# STM32.net
KiCad netlist of a schematic drawn in Altium Designer
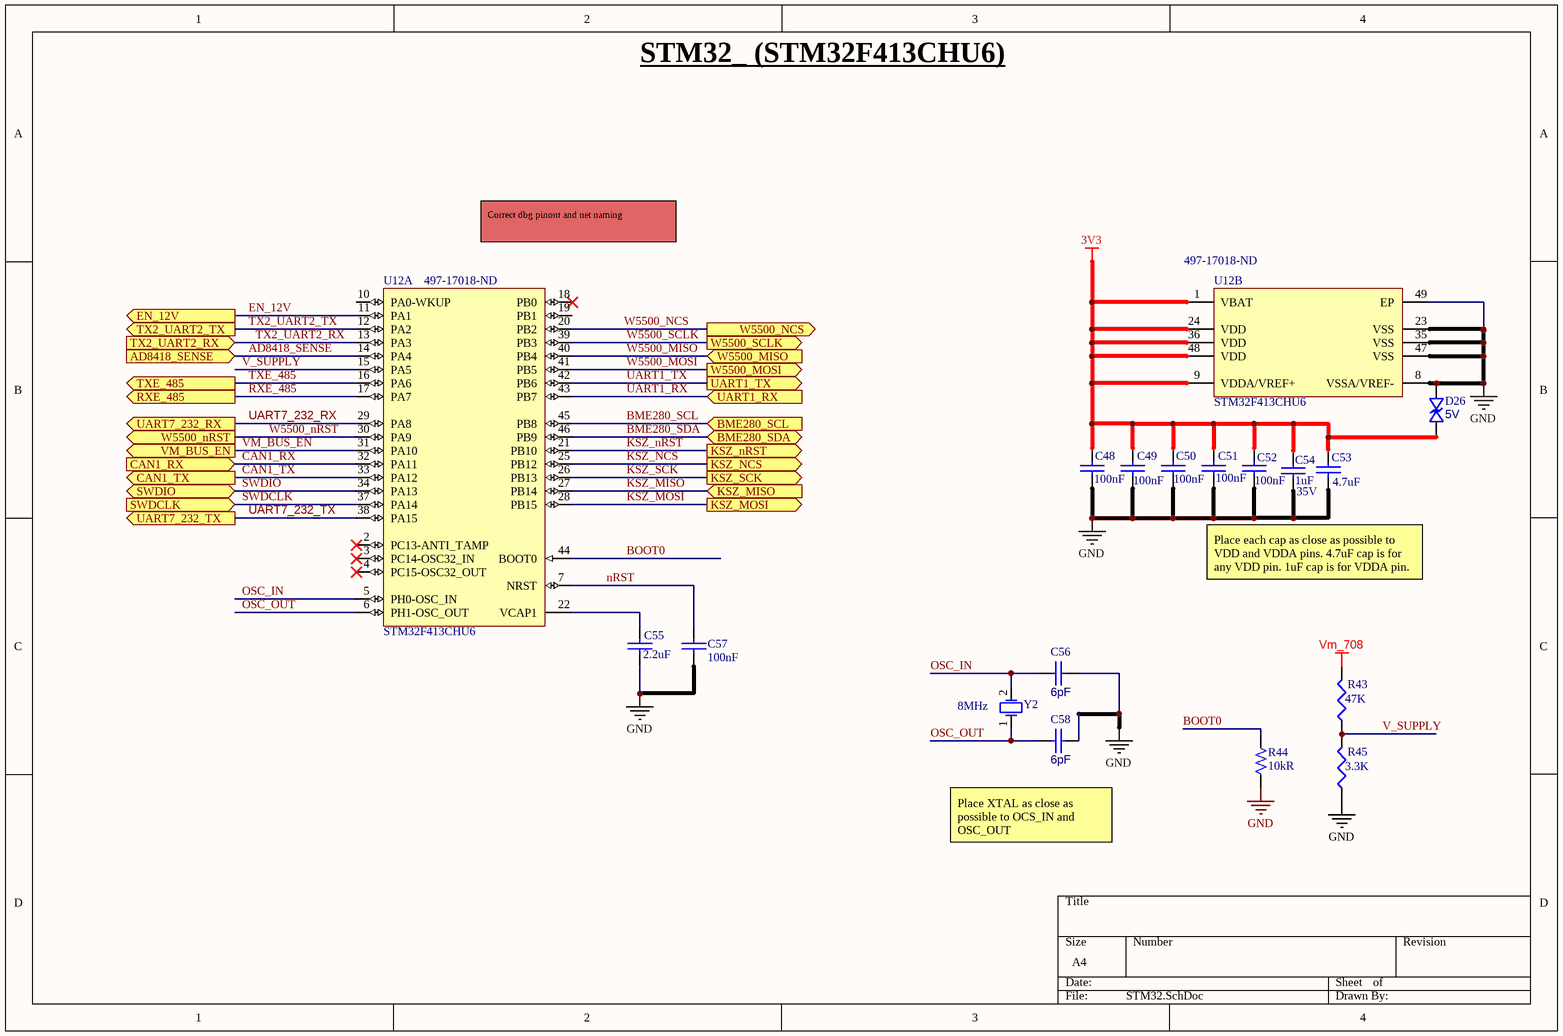
[diagram p0: STM32.SchDoc]

(export (version "E")
  (design (tool "Eeschema 10.0.6"))
  (components
    (comp (ref "C48")
      (value "Capacitor")
      (footprint "CAP0402")
      (fields
        (field (name "MANUFACTURER") "TDK")
        (field (name "MANUFACTURER PART NUMBER") "CGA2B3X7R1H104K050BB")
        (field (name "CAPACITANCE") "100nF")
        (field (name "TOLERANCE") "10%")
      )
      (libsource (lib "") (part "Capacitor_1"))
    )
    (comp (ref "C49")
      (value "Capacitor")
      (footprint "CAP0402")
      (fields
        (field (name "MANUFACTURER") "TDK")
        (field (name "MANUFACTURER PART NUMBER") "CGA2B3X7R1H104K050BB")
        (field (name "CAPACITANCE") "100nF")
        (field (name "TOLERANCE") "10%")
      )
      (libsource (lib "") (part "Capacitor_1"))
    )
    (comp (ref "C50")
      (value "Capacitor")
      (footprint "CAP0402")
      (fields
        (field (name "MANUFACTURER") "TDK")
        (field (name "MANUFACTURER PART NUMBER") "CGA2B3X7R1H104K050BB")
        (field (name "CAPACITANCE") "100nF")
        (field (name "TOLERANCE") "10%")
      )
      (libsource (lib "") (part "Capacitor_1"))
    )
    (comp (ref "C51")
      (value "Capacitor")
      (footprint "CAP0402")
      (fields
        (field (name "MANUFACTURER") "TDK")
        (field (name "MANUFACTURER PART NUMBER") "CGA2B3X7R1H104K050BB")
        (field (name "CAPACITANCE") "100nF")
        (field (name "TOLERANCE") "10%")
      )
      (libsource (lib "") (part "Capacitor_1"))
    )
    (comp (ref "C52")
      (value "Capacitor")
      (footprint "CAP0402")
      (fields
        (field (name "MANUFACTURER") "TDK")
        (field (name "MANUFACTURER PART NUMBER") "CGA2B3X7R1H104K050BB")
        (field (name "CAPACITANCE") "100nF")
        (field (name "TOLERANCE") "10%")
      )
      (libsource (lib "") (part "Capacitor_1"))
    )
    (comp (ref "C53")
      (value "Capacitor")
      (footprint "CAP0402")
      (fields (field (name "CAPACITANCE") "4.7uF"))
      (libsource (lib "") (part "Capacitor_1"))
    )
    (comp (ref "C54")
      (value "Capacitor")
      (footprint "CAP0402")
      (fields (field (name "VOLTAGE RATING") "35V") (field (name "CAPACITANCE") "1uF"))
      (libsource (lib "") (part "Capacitor_1"))
    )
    (comp (ref "C55")
      (value "Capacitor")
      (footprint "CAP0402")
      (fields (field (name "CAPACITANCE") "2.2uF"))
      (libsource (lib "BPL-ShematicLibrary") (part "Capacitor"))
    )
    (comp (ref "C56")
      (value "Capacitor")
      (footprint "CAP0402")
      (description "CAP CER 6PF 100V C0G/NP0 0402")
      (fields (field (name "CAPACITANCE") "6pF"))
      (libsource (lib "BPL-ShematicLibrary") (part "Capacitor"))
    )
    (comp (ref "C57")
      (value "Capacitor")
      (footprint "CAP0402")
      (fields
        (field (name "MANUFACTURER") "TDK")
        (field (name "MANUFACTURER PART NUMBER") "CGA2B3X7R1H104K050BB")
        (field (name "CAPACITANCE") "100nF")
        (field (name "TOLERANCE") "10%")
      )
      (libsource (lib "") (part "Capacitor_1"))
    )
    (comp (ref "C58")
      (value "Capacitor")
      (footprint "CAP0402")
      (description "CAP CER 6PF 100V C0G/NP0 0402")
      (fields (field (name "CAPACITANCE") "6pF"))
      (libsource (lib "BPL-ShematicLibrary") (part "Capacitor"))
    )
    (comp (ref "D26")
      (value "TVS-Bidirectional")
      (footprint "SLP1006P2T")
      (description "TVS DIODE 5V 20V SLP1006P2T")
      (fields (field (name "REVERSE STANDOFF VOLTAGE") "5V"))
      (libsource (lib "BPL-ShematicLibrary") (part "TVS-Bidirectional"))
    )
    (comp (ref "R43")
      (value "47K")
      (footprint "RES0402")
      (description "Resistor")
      (fields
        (field (name "MANUFACTURER") "Yageo")
        (field (name "MANUFACTURER PART NUMBER") "RC0402JR-0747KL")
      )
      (libsource (lib "") (part "Resistor_1"))
    )
    (comp (ref "R44")
      (value "Resistor")
      (footprint "RES0402")
      (fields (field (name "RESISTANCE") "10kR") (field (name "TOLERANCE") "1%"))
      (libsource (lib "BPL-ShematicLibrary") (part "Resistor"))
    )
    (comp (ref "R45")
      (value "3.3K")
      (footprint "RES0402")
      (description "Resistor")
      (fields
        (field (name "MANUFACTURER") "Yageo")
        (field (name "MANUFACTURER PART NUMBER") "RC0402FR-073K3L")
      )
      (libsource (lib "") (part "Resistor_1"))
    )
    (comp (ref "U12")
      (value "STM32F413CHU6")
      (footprint "STM-UFQFPN48_M")
      (fields
        (field (name "MANUFACTURER") "STMicroelectronics")
        (field (name "SUPPLIER PART NUMBER 1") "497-17018-ND")
      )
      (libsource (lib "BPL-ShematicLibrary") (part "STM32F413CHU"))
    )
    (comp (ref "Y2")
      (value "8MHz")
      (footprint "2-SMD-XTAL (3.2x2.5)")
      (description "Crystal Oscillator")
      (fields
        (field (name "MANUFACTURER") "NDK")
        (field (name "MANUFACTURER PART NUMBER") "NX3225GD-8MHZ-STD-CRA-3")
      )
      (libsource (lib "BPL-ShematicLibrary") (part "Crystal Oscillator"))
    )
  )
  (nets
    (net (code "1") (name "/AD8418_SENSE") (class "Default")
      (node (ref "U12") (pin "14") (pinfunction "PA4_14") (pintype "bidirectional"))
    )
    (net (code "2") (name "/BME280_SCL") (class "Default")
      (node (ref "U12") (pin "45") (pinfunction "PB8_45") (pintype "bidirectional"))
    )
    (net (code "3") (name "/BME280_SDA") (class "Default")
      (node (ref "U12") (pin "46") (pinfunction "PB9_46") (pintype "bidirectional"))
    )
    (net (code "4") (name "/BOOT0") (class "Default")
      (node (ref "R44") (pin "1") (pinfunction "1_1") (pintype "passive"))
      (node (ref "U12") (pin "44") (pinfunction "BOOT0_44") (pintype "input"))
    )
    (net (code "5") (name "/CAN1_RX") (class "Default")
      (node (ref "U12") (pin "32") (pinfunction "PA11_32") (pintype "bidirectional"))
    )
    (net (code "6") (name "/CAN1_TX") (class "Default")
      (node (ref "U12") (pin "33") (pinfunction "PA12_33") (pintype "bidirectional"))
    )
    (net (code "7") (name "/EN_12V") (class "Default")
      (node (ref "U12") (pin "11") (pinfunction "PA1_11") (pintype "bidirectional"))
    )
    (net (code "8") (name "/KSZ_MISO") (class "Default")
      (node (ref "U12") (pin "27") (pinfunction "PB14_27") (pintype "bidirectional"))
    )
    (net (code "9") (name "/KSZ_MOSI") (class "Default")
      (node (ref "U12") (pin "28") (pinfunction "PB15_28") (pintype "bidirectional"))
    )
    (net (code "10") (name "/KSZ_NCS") (class "Default")
      (node (ref "U12") (pin "25") (pinfunction "PB12_25") (pintype "bidirectional"))
    )
    (net (code "11") (name "/KSZ_SCK") (class "Default")
      (node (ref "U12") (pin "26") (pinfunction "PB13_26") (pintype "bidirectional"))
    )
    (net (code "12") (name "/KSZ_nRST") (class "Default")
      (node (ref "U12") (pin "21") (pinfunction "PB10_21") (pintype "bidirectional"))
    )
    (net (code "13") (name "/OSC_IN") (class "Default")
      (node (ref "C56") (pin "2") (pinfunction "2_2") (pintype "passive"))
      (node (ref "U12") (pin "5") (pinfunction "PH0-OSC_IN_5") (pintype "bidirectional"))
      (node (ref "Y2") (pin "2") (pinfunction "2_2") (pintype "passive"))
    )
    (net (code "14") (name "/OSC_OUT") (class "Default")
      (node (ref "C58") (pin "2") (pinfunction "2_2") (pintype "passive"))
      (node (ref "U12") (pin "6") (pinfunction "PH1-OSC_OUT_6") (pintype "bidirectional"))
      (node (ref "Y2") (pin "1") (pinfunction "1_1") (pintype "passive"))
    )
    (net (code "15") (name "/RXE_485") (class "Default")
      (node (ref "U12") (pin "17") (pinfunction "PA7_17") (pintype "bidirectional"))
    )
    (net (code "16") (name "/SWDCLK") (class "Default")
      (node (ref "U12") (pin "37") (pinfunction "PA14_37") (pintype "bidirectional"))
    )
    (net (code "17") (name "/SWDIO") (class "Default")
      (node (ref "U12") (pin "34") (pinfunction "PA13_34") (pintype "bidirectional"))
    )
    (net (code "18") (name "/TX2_UART2_RX") (class "Default")
      (node (ref "U12") (pin "13") (pinfunction "PA3_13") (pintype "bidirectional"))
    )
    (net (code "19") (name "/TX2_UART2_TX") (class "Default")
      (node (ref "U12") (pin "12") (pinfunction "PA2_12") (pintype "bidirectional"))
    )
    (net (code "20") (name "/TXE_485") (class "Default")
      (node (ref "U12") (pin "16") (pinfunction "PA6_16") (pintype "bidirectional"))
    )
    (net (code "21") (name "/UART1_RX") (class "Default")
      (node (ref "U12") (pin "43") (pinfunction "PB7_43") (pintype "bidirectional"))
    )
    (net (code "22") (name "/UART1_TX") (class "Default")
      (node (ref "U12") (pin "42") (pinfunction "PB6_42") (pintype "bidirectional"))
    )
    (net (code "23") (name "/UART7_232_RX") (class "Default")
      (node (ref "U12") (pin "29") (pinfunction "PA8_29") (pintype "bidirectional"))
    )
    (net (code "24") (name "/UART7_232_TX") (class "Default")
      (node (ref "U12") (pin "38") (pinfunction "PA15_38") (pintype "bidirectional"))
    )
    (net (code "25") (name "/VM_BUS_EN") (class "Default")
      (node (ref "U12") (pin "31") (pinfunction "PA10_31") (pintype "bidirectional"))
    )
    (net (code "26") (name "/V_SUPPLY") (class "Default")
      (node (ref "R43") (pin "1") (pinfunction "1_1") (pintype "passive"))
      (node (ref "R45") (pin "2") (pinfunction "2_2") (pintype "passive"))
      (node (ref "U12") (pin "15") (pinfunction "PA5_15") (pintype "bidirectional"))
    )
    (net (code "27") (name "/W5500_MISO") (class "Default")
      (node (ref "U12") (pin "40") (pinfunction "PB4_40") (pintype "bidirectional"))
    )
    (net (code "28") (name "/W5500_MOSI") (class "Default")
      (node (ref "U12") (pin "41") (pinfunction "PB5_41") (pintype "bidirectional"))
    )
    (net (code "29") (name "/W5500_NCS") (class "Default")
      (node (ref "U12") (pin "20") (pinfunction "PB2_20") (pintype "bidirectional"))
    )
    (net (code "30") (name "/W5500_SCLK") (class "Default")
      (node (ref "U12") (pin "39") (pinfunction "PB3_39") (pintype "bidirectional"))
    )
    (net (code "31") (name "/W5500_nRST") (class "Default")
      (node (ref "U12") (pin "30") (pinfunction "PA9_30") (pintype "bidirectional"))
    )
    (net (code "32") (name "/nRST") (class "Default")
      (node (ref "C57") (pin "1") (pinfunction "1_1") (pintype "passive"))
      (node (ref "U12") (pin "7") (pinfunction "NRST_7") (pintype "bidirectional"))
    )
    (net (code "33") (name "3V3") (class "Default")
      (node (ref "C48") (pin "1") (pinfunction "1_1") (pintype "passive"))
      (node (ref "C49") (pin "1") (pinfunction "1_1") (pintype "passive"))
      (node (ref "C50") (pin "1") (pinfunction "1_1") (pintype "passive"))
      (node (ref "C51") (pin "1") (pinfunction "1_1") (pintype "passive"))
      (node (ref "C52") (pin "1") (pinfunction "1_1") (pintype "passive"))
      (node (ref "C53") (pin "1") (pinfunction "1_1") (pintype "passive"))
      (node (ref "C54") (pin "2") (pinfunction "2_2") (pintype "passive"))
      (node (ref "D26") (pin "2") (pinfunction "2_2") (pintype "passive"))
      (node (ref "U12") (pin "1") (pinfunction "VBAT_1") (pintype "power_in"))
      (node (ref "U12") (pin "24") (pinfunction "VDD_24") (pintype "power_in"))
      (node (ref "U12") (pin "36") (pinfunction "VDD_36") (pintype "power_in"))
      (node (ref "U12") (pin "48") (pinfunction "VDD_48") (pintype "power_in"))
      (node (ref "U12") (pin "9") (pinfunction "VDDA/VREF+_9") (pintype "power_in"))
    )
    (net (code "34") (name "GND") (class "Default")
      (node (ref "C48") (pin "2") (pinfunction "2_2") (pintype "passive"))
      (node (ref "C49") (pin "2") (pinfunction "2_2") (pintype "passive"))
      (node (ref "C50") (pin "2") (pinfunction "2_2") (pintype "passive"))
      (node (ref "C51") (pin "2") (pinfunction "2_2") (pintype "passive"))
      (node (ref "C52") (pin "2") (pinfunction "2_2") (pintype "passive"))
      (node (ref "C53") (pin "2") (pinfunction "2_2") (pintype "passive"))
      (node (ref "C54") (pin "1") (pinfunction "1_1") (pintype "passive"))
      (node (ref "C55") (pin "2") (pinfunction "2_2") (pintype "passive"))
      (node (ref "C56") (pin "1") (pinfunction "1_1") (pintype "passive"))
      (node (ref "C57") (pin "2") (pinfunction "2_2") (pintype "passive"))
      (node (ref "C58") (pin "1") (pinfunction "1_1") (pintype "passive"))
      (node (ref "D26") (pin "1") (pinfunction "1_1") (pintype "passive"))
      (node (ref "R44") (pin "2") (pinfunction "2_2") (pintype "passive"))
      (node (ref "R45") (pin "1") (pinfunction "1_1") (pintype "passive"))
      (node (ref "U12") (pin "23") (pinfunction "VSS_23") (pintype "power_in"))
      (node (ref "U12") (pin "35") (pinfunction "VSS_35") (pintype "power_in"))
      (node (ref "U12") (pin "47") (pinfunction "VSS_47") (pintype "power_in"))
      (node (ref "U12") (pin "49") (pinfunction "EP_49") (pintype "power_in"))
      (node (ref "U12") (pin "8") (pinfunction "VSSA/VREF-_8") (pintype "power_in"))
    )
    (net (code "35") (name "Net-(U12A-VCAP1)") (class "Default")
      (node (ref "C55") (pin "1") (pinfunction "1_1") (pintype "passive"))
      (node (ref "U12") (pin "22") (pinfunction "VCAP1_22") (pintype "power_in"))
    )
    (net (code "36") (name "Vm_708") (class "Default")
      (node (ref "R43") (pin "2") (pinfunction "2_2") (pintype "passive"))
    )
    (net (code "37") (name "unconnected-(U12A-PA0-WKUP-Pad10)") (class "Default")
      (node (ref "U12") (pin "10") (pinfunction "PA0-WKUP_10") (pintype "bidirectional"))
    )
    (net (code "38") (name "unconnected-(U12A-PB0-Pad18)") (class "Default")
      (node (ref "U12") (pin "18") (pinfunction "PB0_18") (pintype "bidirectional+no_connect"))
    )
    (net (code "39") (name "unconnected-(U12A-PB1-Pad19)") (class "Default")
      (node (ref "U12") (pin "19") (pinfunction "PB1_19") (pintype "bidirectional"))
    )
    (net (code "40") (name "unconnected-(U12A-PC13-ANTI_TAMP-Pad2)") (class "Default")
      (node (ref "U12") (pin "2") (pinfunction "PC13-ANTI_TAMP_2") (pintype "bidirectional+no_connect"))
    )
    (net (code "41") (name "unconnected-(U12A-PC14-OSC32_IN-Pad3)") (class "Default")
      (node (ref "U12") (pin "3") (pinfunction "PC14-OSC32_IN_3") (pintype "bidirectional+no_connect"))
    )
    (net (code "42") (name "unconnected-(U12A-PC15-OSC32_OUT-Pad4)") (class "Default")
      (node (ref "U12") (pin "4") (pinfunction "PC15-OSC32_OUT_4") (pintype "bidirectional+no_connect"))
    )
  )
)
